# Power_CAN.net
KiCad netlist of a schematic drawn in Altium Designer
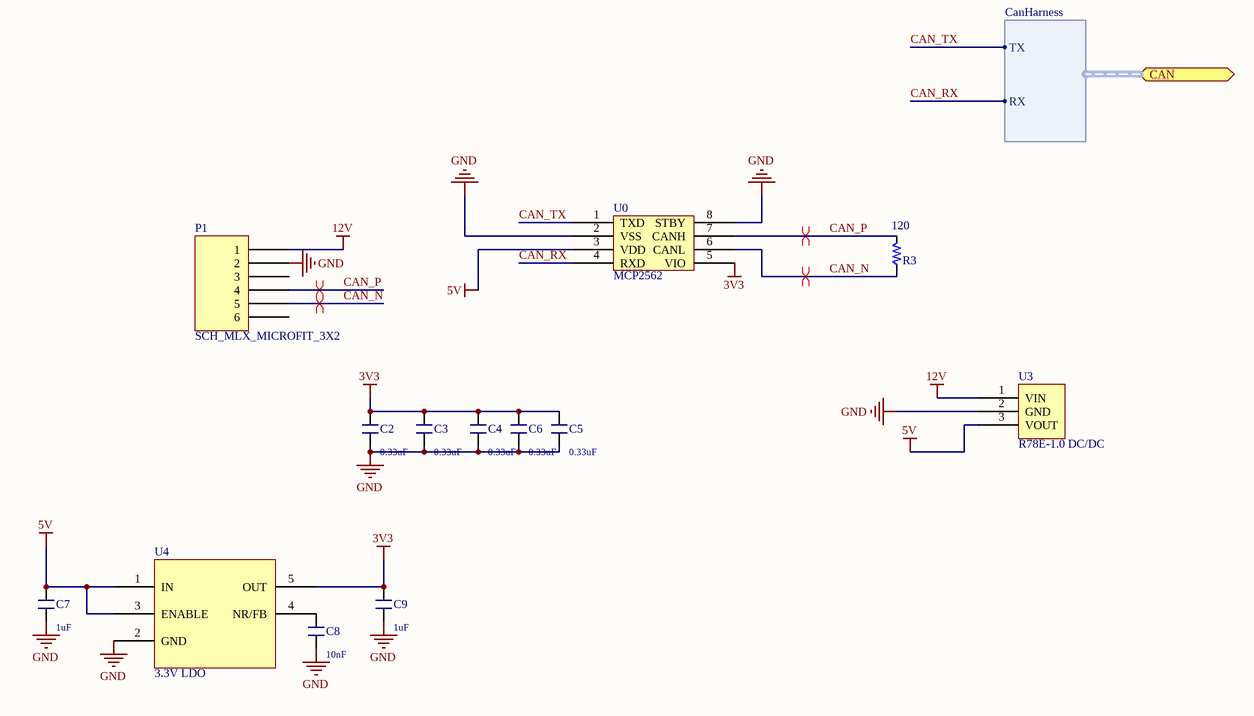
[diagram p0: Power&CAN.SchDoc]

(export (version "E")
  (design (tool "Eeschema 10.0.6"))
  (components
    (comp (ref "C2")
      (value "SCH_GENERIC_CAPACITOR_0603")
      (footprint "PCB_GENERIC_SMD_0603")
      (description "Generic SMD capacitor 0603")
      (fields (field (name "TOLERANCE") "*%") (field (name "CAPACITANCE") "0.33uF"))
      (libsource (lib "Generic 0603 Capacitor") (part "SCH_GENERIC_CAPACITOR_0603"))
    )
    (comp (ref "C3")
      (value "SCH_GENERIC_CAPACITOR_0603")
      (footprint "PCB_GENERIC_SMD_0603")
      (description "Generic SMD capacitor 0603")
      (fields (field (name "TOLERANCE") "*%") (field (name "CAPACITANCE") "0.33uF"))
      (libsource (lib "Generic 0603 Capacitor") (part "SCH_GENERIC_CAPACITOR_0603"))
    )
    (comp (ref "C4")
      (value "SCH_GENERIC_CAPACITOR_0603")
      (footprint "PCB_GENERIC_SMD_0603")
      (description "Generic SMD capacitor 0603")
      (fields (field (name "TOLERANCE") "*%") (field (name "CAPACITANCE") "0.33uF"))
      (libsource (lib "Generic 0603 Capacitor") (part "SCH_GENERIC_CAPACITOR_0603"))
    )
    (comp (ref "C5")
      (value "SCH_GENERIC_CAPACITOR_0603")
      (footprint "PCB_GENERIC_SMD_0603")
      (description "Generic SMD capacitor 0603")
      (fields (field (name "TOLERANCE") "*%") (field (name "CAPACITANCE") "0.33uF"))
      (libsource (lib "Generic 0603 Capacitor") (part "SCH_GENERIC_CAPACITOR_0603"))
    )
    (comp (ref "C6")
      (value "SCH_GENERIC_CAPACITOR_0603")
      (footprint "PCB_GENERIC_SMD_0603")
      (description "Generic SMD capacitor 0603")
      (fields (field (name "TOLERANCE") "*%") (field (name "CAPACITANCE") "0.33uF"))
      (libsource (lib "Generic 0603 Capacitor") (part "SCH_GENERIC_CAPACITOR_0603"))
    )
    (comp (ref "C7")
      (value "SCH_GENERIC_CAPACITOR_0603")
      (footprint "PCB_GENERIC_SMD_0603")
      (description "Generic SMD capacitor 0603")
      (fields (field (name "TOLERANCE") "*%") (field (name "CAPACITANCE") "1uF"))
      (libsource (lib "Generic 0603 Capacitor") (part "SCH_GENERIC_CAPACITOR_0603"))
    )
    (comp (ref "C8")
      (value "SCH_GENERIC_CAPACITOR_0603")
      (footprint "PCB_GENERIC_SMD_0603")
      (description "Generic SMD capacitor 0603")
      (fields (field (name "TOLERANCE") "*%") (field (name "CAPACITANCE") "10nF"))
      (libsource (lib "Generic 0603 Capacitor") (part "SCH_GENERIC_CAPACITOR_0603"))
    )
    (comp (ref "C9")
      (value "SCH_GENERIC_CAPACITOR_0603")
      (footprint "PCB_GENERIC_SMD_0603")
      (description "Generic SMD capacitor 0603")
      (fields (field (name "TOLERANCE") "*%") (field (name "CAPACITANCE") "1uF"))
      (libsource (lib "Generic 0603 Capacitor") (part "SCH_GENERIC_CAPACITOR_0603"))
    )
    (comp (ref "P1")
      (value "SCH_MLX_MICROFIT_3X2")
      (footprint "PCB_MLX_MICROFIT_3X2")
      (libsource (lib "Molex Microfit 3.0 3x2") (part "SCH_MLX_MICROFIT_3X2"))
    )
    (comp (ref "R3")
      (value "SCH_GENERIC_RESISTOR_0603")
      (footprint "PCB_GENERIC_SMD_0603")
      (description "Generic SMD resistor 0603")
      (fields (field (name "RESISTANCE") "120"))
      (libsource (lib "Generic 0603 Resistor") (part "SCH_GENERIC_RESISTOR_0603"))
    )
    (comp (ref "U0")
      (value "MCP2562")
      (footprint "SOIC127P600X175-8N")
      (description "1/1 Transceiver Full CAN 8-SOIC")
      (libsource (lib "Microchip MCP2562") (part "MCP2562"))
    )
    (comp (ref "U3")
      (value "R78E-1.0 DC/DC")
      (footprint "R78-1.0")
      (libsource (lib "Recom R78E-1.0") (part "R78E-1.0"))
    )
    (comp (ref "U4")
      (value "3.3V LDO")
      (footprint "SOT95P280X145-5N")
      (description "Linear Voltage Regulator IC Positive Fixed 1 Output 3.3V 400mA SOT-23-5")
      (libsource (lib "3V3LDO_TPS73633DBVR_SOT23-5") (part "3V3LDO_TPS73633DBVR_SOT23-5"))
    )
  )
  (nets
    (net (code "2") (name "/CAN_N") (class "Default")
      (node (ref "P1") (pin "5") (pinfunction "5_5") (pintype "passive"))
      (node (ref "R3") (pin "1") (pinfunction "1_1") (pintype "passive"))
      (node (ref "U0") (pin "6") (pinfunction "CANL_6") (pintype "passive"))
    )
    (net (code "3") (name "/CAN_P") (class "Default")
      (node (ref "P1") (pin "4") (pinfunction "4_4") (pintype "passive"))
      (node (ref "R3") (pin "2") (pinfunction "2_2") (pintype "passive"))
      (node (ref "U0") (pin "7") (pinfunction "CANH_7") (pintype "passive"))
    )
    (net (code "4") (name "/CAN_RX") (class "Default")
      (node (ref "U0") (pin "4") (pinfunction "RXD_4") (pintype "passive"))
    )
    (net (code "5") (name "/CAN_TX") (class "Default")
      (node (ref "U0") (pin "1") (pinfunction "TXD_1") (pintype "passive"))
    )
    (net (code "7") (name "3V3") (class "Default")
      (node (ref "C2") (pin "2") (pinfunction "2_2") (pintype "passive"))
      (node (ref "C3") (pin "2") (pinfunction "2_2") (pintype "passive"))
      (node (ref "C4") (pin "2") (pinfunction "2_2") (pintype "passive"))
      (node (ref "C5") (pin "2") (pinfunction "2_2") (pintype "passive"))
      (node (ref "C6") (pin "2") (pinfunction "2_2") (pintype "passive"))
      (node (ref "C9") (pin "2") (pinfunction "2_2") (pintype "passive"))
      (node (ref "U0") (pin "5") (pinfunction "VIO_5") (pintype "passive"))
      (node (ref "U4") (pin "5") (pinfunction "OUT_5") (pintype "power_in"))
    )
    (net (code "8") (name "5V") (class "Default")
      (node (ref "C7") (pin "2") (pinfunction "2_2") (pintype "passive"))
      (node (ref "U0") (pin "3") (pinfunction "VDD_3") (pintype "passive"))
      (node (ref "U3") (pin "3") (pinfunction "VOUT_3") (pintype "passive"))
      (node (ref "U4") (pin "1") (pinfunction "IN_1") (pintype "power_in"))
      (node (ref "U4") (pin "3") (pinfunction "ENABLE_3") (pintype "power_in"))
    )
    (net (code "9") (name "12V") (class "Default")
      (node (ref "P1") (pin "1") (pinfunction "1_1") (pintype "passive"))
      (node (ref "U3") (pin "1") (pinfunction "VIN_1") (pintype "passive"))
    )
    (net (code "10") (name "GND") (class "Default")
      (node (ref "C2") (pin "1") (pinfunction "1_1") (pintype "passive"))
      (node (ref "C3") (pin "1") (pinfunction "1_1") (pintype "passive"))
      (node (ref "C4") (pin "1") (pinfunction "1_1") (pintype "passive"))
      (node (ref "C5") (pin "1") (pinfunction "1_1") (pintype "passive"))
      (node (ref "C6") (pin "1") (pinfunction "1_1") (pintype "passive"))
      (node (ref "C7") (pin "1") (pinfunction "1_1") (pintype "passive"))
      (node (ref "C8") (pin "1") (pinfunction "1_1") (pintype "passive"))
      (node (ref "C9") (pin "1") (pinfunction "1_1") (pintype "passive"))
      (node (ref "P1") (pin "2") (pinfunction "2_2") (pintype "passive"))
      (node (ref "U0") (pin "2") (pinfunction "VSS_2") (pintype "passive"))
      (node (ref "U0") (pin "8") (pinfunction "STBY_8") (pintype "passive"))
      (node (ref "U3") (pin "2") (pinfunction "GND_2") (pintype "passive"))
      (node (ref "U4") (pin "2") (pinfunction "GND_2") (pintype "power_in"))
    )
    (net (code "11") (name "Net-(U4-NR{slash}FB)") (class "Default")
      (node (ref "C8") (pin "2") (pinfunction "2_2") (pintype "passive"))
      (node (ref "U4") (pin "4") (pinfunction "NR/FB_4") (pintype "power_in"))
    )
    (net (code "12") (name "unconnected-(P1-Pad3)") (class "Default")
      (node (ref "P1") (pin "3") (pinfunction "3_3") (pintype "passive"))
    )
    (net (code "13") (name "unconnected-(P1-Pad6)") (class "Default")
      (node (ref "P1") (pin "6") (pinfunction "6_6") (pintype "passive"))
    )
  )
)
